# DRIVER_B.net
KiCad netlist of a schematic drawn in Altium Designer
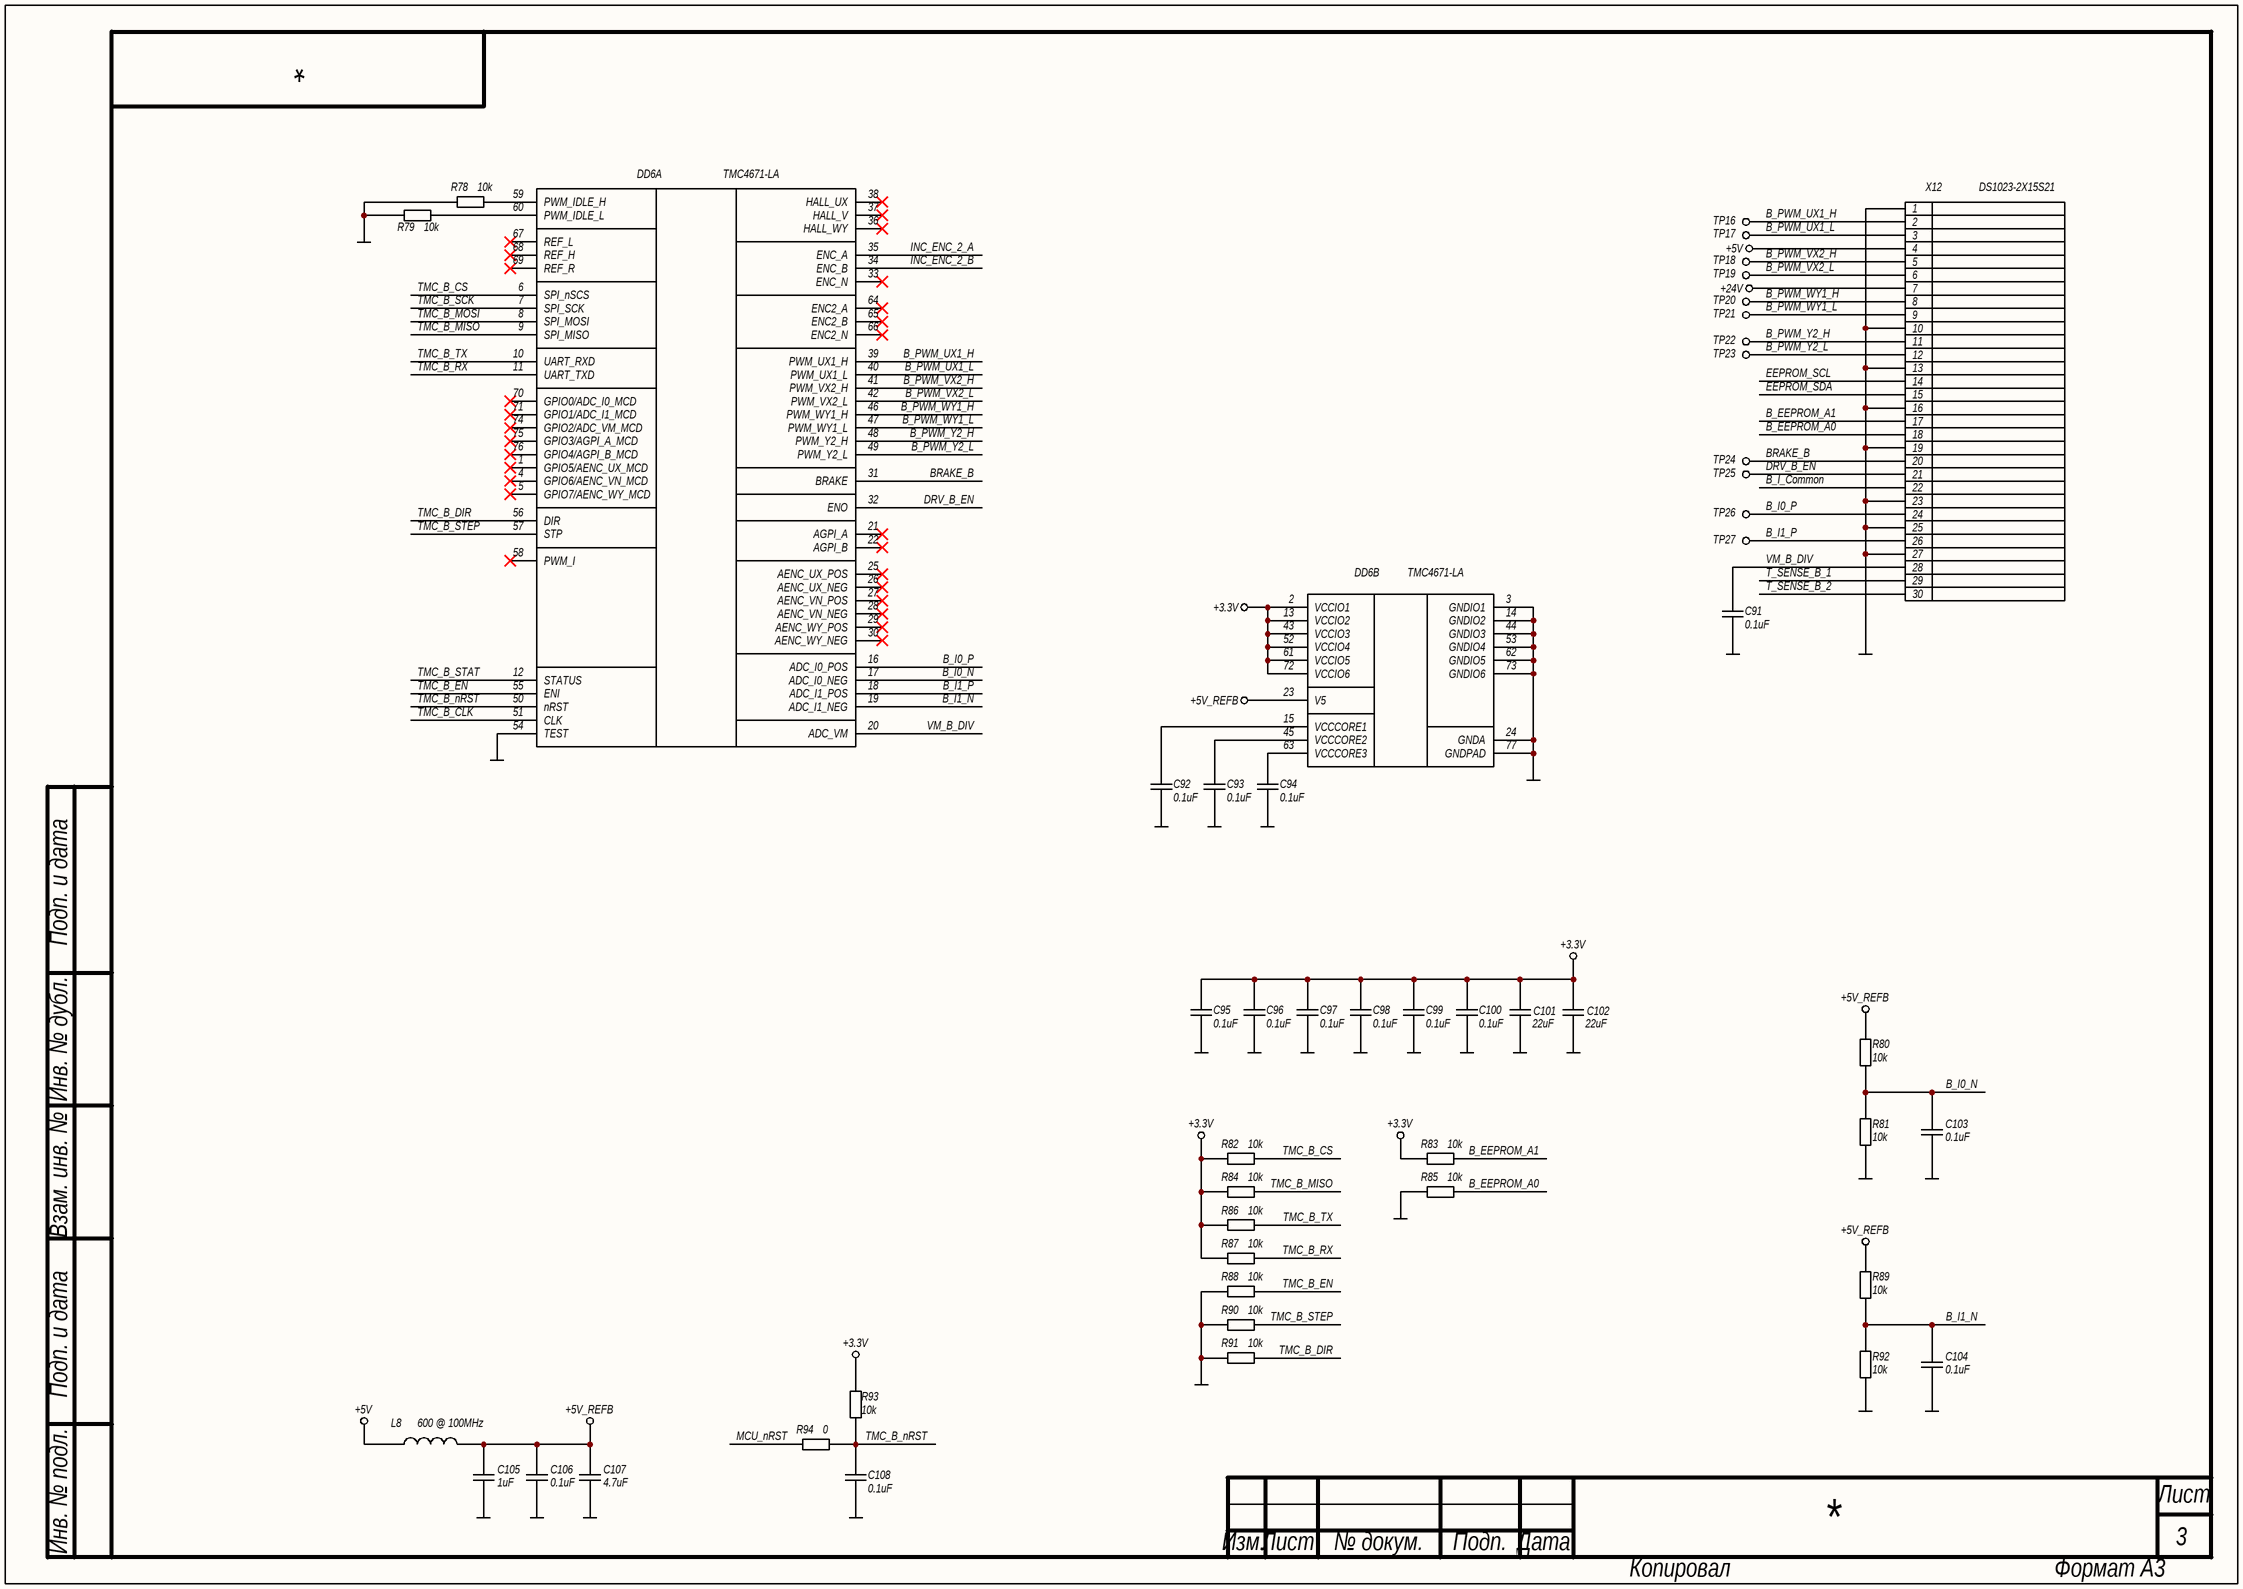
[diagram p0: DRIVER_B.SchDoc]

(export (version "E")
  (design (tool "Eeschema 10.0.6"))
  (components
    (comp (ref "C91")
      (value "0.1uF")
      (footprint "C0603N")
      (description "Конденсатор")
      (libsource (lib "Components Library") (part "CAP_FIXED"))
    )
    (comp (ref "C92")
      (value "0.1uF")
      (footprint "C0603N")
      (description "Конденсатор")
      (libsource (lib "Components Library") (part "CAP_FIXED"))
    )
    (comp (ref "C93")
      (value "0.1uF")
      (footprint "C0603N")
      (description "Конденсатор")
      (libsource (lib "Components Library") (part "CAP_FIXED"))
    )
    (comp (ref "C94")
      (value "0.1uF")
      (footprint "C0603N")
      (description "Конденсатор")
      (libsource (lib "Components Library") (part "CAP_FIXED"))
    )
    (comp (ref "C95")
      (value "0.1uF")
      (footprint "C0603N")
      (description "Конденсатор")
      (libsource (lib "Components Library") (part "CAP_FIXED"))
    )
    (comp (ref "C96")
      (value "0.1uF")
      (footprint "C0603N")
      (description "Конденсатор")
      (libsource (lib "Components Library") (part "CAP_FIXED"))
    )
    (comp (ref "C97")
      (value "0.1uF")
      (footprint "C0603N")
      (description "Конденсатор")
      (libsource (lib "Components Library") (part "CAP_FIXED"))
    )
    (comp (ref "C98")
      (value "0.1uF")
      (footprint "C0603N")
      (description "Конденсатор")
      (libsource (lib "Components Library") (part "CAP_FIXED"))
    )
    (comp (ref "C99")
      (value "0.1uF")
      (footprint "C0603N")
      (description "Конденсатор")
      (libsource (lib "Components Library") (part "CAP_FIXED"))
    )
    (comp (ref "C100")
      (value "0.1uF")
      (footprint "C0603N")
      (description "Конденсатор")
      (libsource (lib "Components Library") (part "CAP_FIXED"))
    )
    (comp (ref "C101")
      (value "22uF")
      (footprint "C0805N")
      (description "Конденсатор")
      (libsource (lib "Components Library") (part "CAP_FIXED"))
    )
    (comp (ref "C102")
      (value "22uF")
      (footprint "C0805N")
      (description "Конденсатор")
      (libsource (lib "Components Library") (part "CAP_FIXED"))
    )
    (comp (ref "C103")
      (value "0.1uF")
      (footprint "C0603N")
      (description "Конденсатор")
      (libsource (lib "Components Library") (part "CAP_FIXED"))
    )
    (comp (ref "C104")
      (value "0.1uF")
      (footprint "C0603N")
      (description "Конденсатор")
      (libsource (lib "Components Library") (part "CAP_FIXED"))
    )
    (comp (ref "C105")
      (value "1uF")
      (footprint "C0603N")
      (description "Конденсатор")
      (libsource (lib "Components Library") (part "CAP_FIXED"))
    )
    (comp (ref "C106")
      (value "0.1uF")
      (footprint "C0603N")
      (description "Конденсатор")
      (libsource (lib "Components Library") (part "CAP_FIXED"))
    )
    (comp (ref "C107")
      (value "4.7uF")
      (footprint "C0603N")
      (description "Конденсатор")
      (libsource (lib "Components Library") (part "CAP_FIXED"))
    )
    (comp (ref "C108")
      (value "0.1uF")
      (footprint "C0603N")
      (description "Конденсатор")
      (libsource (lib "Components Library") (part "CAP_FIXED"))
    )
    (comp (ref "DD6")
      (value "TMC4671-LA")
      (footprint "QFN76-EP")
      (description "Микросхема драйвер двигателя")
      (libsource (lib "Components Library") (part "TMC4671-LA"))
    )
    (comp (ref "L8")
      (value "600 @ 100MHz")
      (footprint "FB0603N")
      (description "Фильтр ЭМП индуктивный")
      (libsource (lib "Components Library") (part "IND_FILTER"))
    )
    (comp (ref "R78")
      (value "10k")
      (footprint "R0603N")
      (description "Резистор")
      (libsource (lib "Components Library") (part "RES_FIXED"))
    )
    (comp (ref "R79")
      (value "10k")
      (footprint "R0603N")
      (description "Резистор")
      (libsource (lib "Components Library") (part "RES_FIXED"))
    )
    (comp (ref "R80")
      (value "10k")
      (footprint "R0603N")
      (description "Резистор")
      (libsource (lib "") (part "RES_FIXED_1"))
    )
    (comp (ref "R81")
      (value "10k")
      (footprint "R0603N")
      (description "Резистор")
      (libsource (lib "") (part "RES_FIXED_1"))
    )
    (comp (ref "R82")
      (value "10k")
      (footprint "R0603N")
      (description "Резистор")
      (libsource (lib "Components Library") (part "RES_FIXED"))
    )
    (comp (ref "R83")
      (value "10k")
      (footprint "R0603N")
      (description "Резистор")
      (libsource (lib "Components Library") (part "RES_FIXED"))
    )
    (comp (ref "R84")
      (value "10k")
      (footprint "R0603N")
      (description "Резистор")
      (libsource (lib "Components Library") (part "RES_FIXED"))
    )
    (comp (ref "R85")
      (value "10k")
      (footprint "R0603N")
      (description "Резистор")
      (libsource (lib "Components Library") (part "RES_FIXED"))
    )
    (comp (ref "R86")
      (value "10k")
      (footprint "R0603N")
      (description "Резистор")
      (libsource (lib "Components Library") (part "RES_FIXED"))
    )
    (comp (ref "R87")
      (value "10k")
      (footprint "R0603N")
      (description "Резистор")
      (libsource (lib "Components Library") (part "RES_FIXED"))
    )
    (comp (ref "R88")
      (value "10k")
      (footprint "R0603N")
      (description "Резистор")
      (libsource (lib "Components Library") (part "RES_FIXED"))
    )
    (comp (ref "R89")
      (value "10k")
      (footprint "R0603N")
      (description "Резистор")
      (libsource (lib "") (part "RES_FIXED_1"))
    )
    (comp (ref "R90")
      (value "10k")
      (footprint "R0603N")
      (description "Резистор")
      (libsource (lib "Components Library") (part "RES_FIXED"))
    )
    (comp (ref "R91")
      (value "10k")
      (footprint "R0603N")
      (description "Резистор")
      (libsource (lib "Components Library") (part "RES_FIXED"))
    )
    (comp (ref "R92")
      (value "10k")
      (footprint "R0603N")
      (description "Резистор")
      (libsource (lib "") (part "RES_FIXED_1"))
    )
    (comp (ref "R93")
      (value "10k")
      (footprint "R0603N")
      (description "Резистор")
      (libsource (lib "") (part "RES_FIXED_1"))
    )
    (comp (ref "R94")
      (value "0")
      (footprint "R0603N")
      (description "Резистор")
      (libsource (lib "Components Library") (part "RES_FIXED"))
    )
    (comp (ref "TP16")
      (value "TEST_POINT")
      (footprint "TP_RPAD_0.8MM")
      (description "Контрольная точка")
      (libsource (lib "Components Library") (part "TEST_POINT"))
    )
    (comp (ref "TP17")
      (value "TEST_POINT")
      (footprint "TP_RPAD_0.8MM")
      (description "Контрольная точка")
      (libsource (lib "Components Library") (part "TEST_POINT"))
    )
    (comp (ref "TP18")
      (value "TEST_POINT")
      (footprint "TP_RPAD_0.8MM")
      (description "Контрольная точка")
      (libsource (lib "Components Library") (part "TEST_POINT"))
    )
    (comp (ref "TP19")
      (value "TEST_POINT")
      (footprint "TP_RPAD_0.8MM")
      (description "Контрольная точка")
      (libsource (lib "Components Library") (part "TEST_POINT"))
    )
    (comp (ref "TP20")
      (value "TEST_POINT")
      (footprint "TP_RPAD_0.8MM")
      (description "Контрольная точка")
      (libsource (lib "Components Library") (part "TEST_POINT"))
    )
    (comp (ref "TP21")
      (value "TEST_POINT")
      (footprint "TP_RPAD_0.8MM")
      (description "Контрольная точка")
      (libsource (lib "Components Library") (part "TEST_POINT"))
    )
    (comp (ref "TP22")
      (value "TEST_POINT")
      (footprint "TP_RPAD_0.8MM")
      (description "Контрольная точка")
      (libsource (lib "Components Library") (part "TEST_POINT"))
    )
    (comp (ref "TP23")
      (value "TEST_POINT")
      (footprint "TP_RPAD_0.8MM")
      (description "Контрольная точка")
      (libsource (lib "Components Library") (part "TEST_POINT"))
    )
    (comp (ref "TP24")
      (value "TEST_POINT")
      (footprint "TP_RPAD_0.8MM")
      (description "Контрольная точка")
      (libsource (lib "Components Library") (part "TEST_POINT"))
    )
    (comp (ref "TP25")
      (value "TEST_POINT")
      (footprint "TP_RPAD_0.8MM")
      (description "Контрольная точка")
      (libsource (lib "Components Library") (part "TEST_POINT"))
    )
    (comp (ref "TP26")
      (value "TEST_POINT")
      (footprint "TP_RPAD_0.8MM")
      (description "Контрольная точка")
      (libsource (lib "Components Library") (part "TEST_POINT"))
    )
    (comp (ref "TP27")
      (value "TEST_POINT")
      (footprint "TP_RPAD_0.8MM")
      (description "Контрольная точка")
      (libsource (lib "Components Library") (part "TEST_POINT"))
    )
    (comp (ref "X12")
      (value "DS1023-2X15S21")
      (footprint "2.54_2X15_SOCKET_HEADER")
      (description "Разъем, 30 контактов")
      (libsource (lib "Components Library") (part "Connector 30"))
    )
  )
  (nets
    (net (code "1") (name "+3.3V") (class "Default")
      (node (ref "C100") (pin "2") (pinfunction "2_2") (pintype "passive"))
      (node (ref "C101") (pin "2") (pinfunction "2_2") (pintype "passive"))
      (node (ref "C102") (pin "2") (pinfunction "2_2") (pintype "passive"))
      (node (ref "C95") (pin "2") (pinfunction "2_2") (pintype "passive"))
      (node (ref "C96") (pin "2") (pinfunction "2_2") (pintype "passive"))
      (node (ref "C97") (pin "2") (pinfunction "2_2") (pintype "passive"))
      (node (ref "C98") (pin "2") (pinfunction "2_2") (pintype "passive"))
      (node (ref "C99") (pin "2") (pinfunction "2_2") (pintype "passive"))
      (node (ref "DD6") (pin "13") (pinfunction "VCCIO2_13") (pintype "power_in"))
      (node (ref "DD6") (pin "2") (pinfunction "VCCIO1_2") (pintype "power_in"))
      (node (ref "DD6") (pin "43") (pinfunction "VCCIO3_43") (pintype "power_in"))
      (node (ref "DD6") (pin "52") (pinfunction "VCCIO4_52") (pintype "power_in"))
      (node (ref "DD6") (pin "61") (pinfunction "VCCIO5_61") (pintype "power_in"))
      (node (ref "DD6") (pin "72") (pinfunction "VCCIO6_72") (pintype "power_in"))
      (node (ref "R82") (pin "2") (pinfunction "2_2") (pintype "passive"))
      (node (ref "R83") (pin "2") (pinfunction "2_2") (pintype "passive"))
      (node (ref "R84") (pin "2") (pinfunction "2_2") (pintype "passive"))
      (node (ref "R86") (pin "2") (pinfunction "2_2") (pintype "passive"))
      (node (ref "R87") (pin "2") (pinfunction "2_2") (pintype "passive"))
      (node (ref "R93") (pin "2") (pinfunction "2_2") (pintype "passive"))
    )
    (net (code "2") (name "+5V") (class "Default")
      (node (ref "L8") (pin "1") (pinfunction "1_1") (pintype "passive"))
      (node (ref "X12") (pin "4") (pinfunction "4_4") (pintype "power_in"))
    )
    (net (code "3") (name "+5V_REFB") (class "Default")
      (node (ref "C105") (pin "2") (pinfunction "2_2") (pintype "passive"))
      (node (ref "C106") (pin "2") (pinfunction "2_2") (pintype "passive"))
      (node (ref "C107") (pin "2") (pinfunction "2_2") (pintype "passive"))
      (node (ref "DD6") (pin "23") (pinfunction "V5_23") (pintype "power_in"))
      (node (ref "L8") (pin "2") (pinfunction "2_2") (pintype "passive"))
      (node (ref "R80") (pin "2") (pinfunction "2_2") (pintype "passive"))
      (node (ref "R89") (pin "2") (pinfunction "2_2") (pintype "passive"))
    )
    (net (code "4") (name "+24V") (class "Default")
      (node (ref "X12") (pin "7") (pinfunction "7_7") (pintype "power_in"))
    )
    (net (code "5") (name "/BRAKE_B") (class "Default")
      (node (ref "DD6") (pin "31") (pinfunction "BRAKE_31") (pintype "power_in"))
      (node (ref "TP24") (pin "1") (pinfunction "1_1") (pintype "passive"))
      (node (ref "X12") (pin "20") (pinfunction "20_20") (pintype "power_in"))
    )
    (net (code "6") (name "/B_EEPROM_A0") (class "Default")
      (node (ref "R85") (pin "1") (pinfunction "1_1") (pintype "passive"))
      (node (ref "X12") (pin "18") (pinfunction "18_18") (pintype "power_in"))
    )
    (net (code "7") (name "/B_EEPROM_A1") (class "Default")
      (node (ref "R83") (pin "1") (pinfunction "1_1") (pintype "passive"))
      (node (ref "X12") (pin "17") (pinfunction "17_17") (pintype "power_in"))
    )
    (net (code "8") (name "/B_I0_N") (class "Default")
      (node (ref "C103") (pin "2") (pinfunction "2_2") (pintype "passive"))
      (node (ref "DD6") (pin "17") (pinfunction "ADC_I0_NEG_17") (pintype "power_in"))
      (node (ref "R80") (pin "1") (pinfunction "1_1") (pintype "passive"))
      (node (ref "R81") (pin "2") (pinfunction "2_2") (pintype "passive"))
    )
    (net (code "9") (name "/B_I0_P") (class "Default")
      (node (ref "DD6") (pin "16") (pinfunction "ADC_I0_POS_16") (pintype "power_in"))
      (node (ref "TP26") (pin "1") (pinfunction "1_1") (pintype "passive"))
      (node (ref "X12") (pin "24") (pinfunction "24_24") (pintype "power_in"))
    )
    (net (code "10") (name "/B_I1_N") (class "Default")
      (node (ref "C104") (pin "2") (pinfunction "2_2") (pintype "passive"))
      (node (ref "DD6") (pin "19") (pinfunction "ADC_I1_NEG_19") (pintype "power_in"))
      (node (ref "R89") (pin "1") (pinfunction "1_1") (pintype "passive"))
      (node (ref "R92") (pin "2") (pinfunction "2_2") (pintype "passive"))
    )
    (net (code "11") (name "/B_I1_P") (class "Default")
      (node (ref "DD6") (pin "18") (pinfunction "ADC_I1_POS_18") (pintype "power_in"))
      (node (ref "TP27") (pin "1") (pinfunction "1_1") (pintype "passive"))
      (node (ref "X12") (pin "26") (pinfunction "26_26") (pintype "power_in"))
    )
    (net (code "12") (name "/B_I_Common") (class "Default")
      (node (ref "X12") (pin "22") (pinfunction "22_22") (pintype "power_in"))
    )
    (net (code "13") (name "/B_PWM_UX1_H") (class "Default")
      (node (ref "DD6") (pin "39") (pinfunction "PWM_UX1_H_39") (pintype "power_in"))
      (node (ref "TP16") (pin "1") (pinfunction "1_1") (pintype "passive"))
      (node (ref "X12") (pin "2") (pinfunction "2_2") (pintype "power_in"))
    )
    (net (code "14") (name "/B_PWM_UX1_L") (class "Default")
      (node (ref "DD6") (pin "40") (pinfunction "PWM_UX1_L_40") (pintype "power_in"))
      (node (ref "TP17") (pin "1") (pinfunction "1_1") (pintype "passive"))
      (node (ref "X12") (pin "3") (pinfunction "3_3") (pintype "power_in"))
    )
    (net (code "15") (name "/B_PWM_VX2_H") (class "Default")
      (node (ref "DD6") (pin "41") (pinfunction "PWM_VX2_H_41") (pintype "power_in"))
      (node (ref "TP18") (pin "1") (pinfunction "1_1") (pintype "passive"))
      (node (ref "X12") (pin "5") (pinfunction "5_5") (pintype "power_in"))
    )
    (net (code "16") (name "/B_PWM_VX2_L") (class "Default")
      (node (ref "DD6") (pin "42") (pinfunction "PWM_VX2_L_42") (pintype "power_in"))
      (node (ref "TP19") (pin "1") (pinfunction "1_1") (pintype "passive"))
      (node (ref "X12") (pin "6") (pinfunction "6_6") (pintype "power_in"))
    )
    (net (code "17") (name "/B_PWM_WY1_H") (class "Default")
      (node (ref "DD6") (pin "46") (pinfunction "PWM_WY1_H_46") (pintype "power_in"))
      (node (ref "TP20") (pin "1") (pinfunction "1_1") (pintype "passive"))
      (node (ref "X12") (pin "8") (pinfunction "8_8") (pintype "power_in"))
    )
    (net (code "18") (name "/B_PWM_WY1_L") (class "Default")
      (node (ref "DD6") (pin "47") (pinfunction "PWM_WY1_L_47") (pintype "power_in"))
      (node (ref "TP21") (pin "1") (pinfunction "1_1") (pintype "passive"))
      (node (ref "X12") (pin "9") (pinfunction "9_9") (pintype "power_in"))
    )
    (net (code "19") (name "/B_PWM_Y2_H") (class "Default")
      (node (ref "DD6") (pin "48") (pinfunction "PWM_Y2_H_48") (pintype "power_in"))
      (node (ref "TP22") (pin "1") (pinfunction "1_1") (pintype "passive"))
      (node (ref "X12") (pin "11") (pinfunction "11_11") (pintype "power_in"))
    )
    (net (code "20") (name "/B_PWM_Y2_L") (class "Default")
      (node (ref "DD6") (pin "49") (pinfunction "PWM_Y2_L_49") (pintype "power_in"))
      (node (ref "TP23") (pin "1") (pinfunction "1_1") (pintype "passive"))
      (node (ref "X12") (pin "12") (pinfunction "12_12") (pintype "power_in"))
    )
    (net (code "21") (name "/DRV_B_EN") (class "Default")
      (node (ref "DD6") (pin "32") (pinfunction "ENO_32") (pintype "power_in"))
      (node (ref "TP25") (pin "1") (pinfunction "1_1") (pintype "passive"))
      (node (ref "X12") (pin "21") (pinfunction "21_21") (pintype "power_in"))
    )
    (net (code "22") (name "/EEPROM_SCL") (class "Default")
      (node (ref "X12") (pin "14") (pinfunction "14_14") (pintype "power_in"))
    )
    (net (code "23") (name "/EEPROM_SDA") (class "Default")
      (node (ref "X12") (pin "15") (pinfunction "15_15") (pintype "power_in"))
    )
    (net (code "24") (name "/INC_ENC_2_A") (class "Default")
      (node (ref "DD6") (pin "35") (pinfunction "ENC_A_35") (pintype "power_in"))
    )
    (net (code "25") (name "/INC_ENC_2_B") (class "Default")
      (node (ref "DD6") (pin "34") (pinfunction "ENC_B_34") (pintype "power_in"))
    )
    (net (code "26") (name "/MCU_nRST") (class "Default")
      (node (ref "R94") (pin "2") (pinfunction "2_2") (pintype "passive"))
    )
    (net (code "27") (name "/TMC_B_CLK") (class "Default")
      (node (ref "DD6") (pin "51") (pinfunction "CLK_51") (pintype "power_in"))
    )
    (net (code "28") (name "/TMC_B_CS") (class "Default")
      (node (ref "DD6") (pin "6") (pinfunction "SPI_nSCS_6") (pintype "power_in"))
      (node (ref "R82") (pin "1") (pinfunction "1_1") (pintype "passive"))
    )
    (net (code "29") (name "/TMC_B_DIR") (class "Default")
      (node (ref "DD6") (pin "56") (pinfunction "DIR_56") (pintype "power_in"))
      (node (ref "R91") (pin "1") (pinfunction "1_1") (pintype "passive"))
    )
    (net (code "30") (name "/TMC_B_EN") (class "Default")
      (node (ref "DD6") (pin "55") (pinfunction "ENI_55") (pintype "power_in"))
      (node (ref "R88") (pin "1") (pinfunction "1_1") (pintype "passive"))
    )
    (net (code "31") (name "/TMC_B_MISO") (class "Default")
      (node (ref "DD6") (pin "9") (pinfunction "SPI_MISO_9") (pintype "power_in"))
      (node (ref "R84") (pin "1") (pinfunction "1_1") (pintype "passive"))
    )
    (net (code "32") (name "/TMC_B_MOSI") (class "Default")
      (node (ref "DD6") (pin "8") (pinfunction "SPI_MOSI_8") (pintype "power_in"))
    )
    (net (code "33") (name "/TMC_B_RX") (class "Default")
      (node (ref "DD6") (pin "11") (pinfunction "UART_TXD_11") (pintype "power_in"))
      (node (ref "R87") (pin "1") (pinfunction "1_1") (pintype "passive"))
    )
    (net (code "34") (name "/TMC_B_SCK") (class "Default")
      (node (ref "DD6") (pin "7") (pinfunction "SPI_SCK_7") (pintype "power_in"))
    )
    (net (code "35") (name "/TMC_B_STAT") (class "Default")
      (node (ref "DD6") (pin "12") (pinfunction "STATUS_12") (pintype "power_in"))
    )
    (net (code "36") (name "/TMC_B_STEP") (class "Default")
      (node (ref "DD6") (pin "57") (pinfunction "STP_57") (pintype "power_in"))
      (node (ref "R90") (pin "1") (pinfunction "1_1") (pintype "passive"))
    )
    (net (code "37") (name "/TMC_B_TX") (class "Default")
      (node (ref "DD6") (pin "10") (pinfunction "UART_RXD_10") (pintype "power_in"))
      (node (ref "R86") (pin "1") (pinfunction "1_1") (pintype "passive"))
    )
    (net (code "38") (name "/TMC_B_nRST") (class "Default")
      (node (ref "C108") (pin "2") (pinfunction "2_2") (pintype "passive"))
      (node (ref "DD6") (pin "50") (pinfunction "nRST_50") (pintype "power_in"))
      (node (ref "R93") (pin "1") (pinfunction "1_1") (pintype "passive"))
      (node (ref "R94") (pin "1") (pinfunction "1_1") (pintype "passive"))
    )
    (net (code "39") (name "/T_SENSE_B_1") (class "Default")
      (node (ref "X12") (pin "29") (pinfunction "29_29") (pintype "power_in"))
    )
    (net (code "40") (name "/T_SENSE_B_2") (class "Default")
      (node (ref "X12") (pin "30") (pinfunction "30_30") (pintype "power_in"))
    )
    (net (code "41") (name "/VM_B_DIV") (class "Default")
      (node (ref "C91") (pin "2") (pinfunction "2_2") (pintype "passive"))
      (node (ref "DD6") (pin "20") (pinfunction "ADC_VM_20") (pintype "power_in"))
      (node (ref "X12") (pin "28") (pinfunction "28_28") (pintype "power_in"))
    )
    (net (code "42") (name "GND") (class "Default")
      (node (ref "C100") (pin "1") (pinfunction "1_1") (pintype "passive"))
      (node (ref "C101") (pin "1") (pinfunction "1_1") (pintype "passive"))
      (node (ref "C102") (pin "1") (pinfunction "1_1") (pintype "passive"))
      (node (ref "C103") (pin "1") (pinfunction "1_1") (pintype "passive"))
      (node (ref "C104") (pin "1") (pinfunction "1_1") (pintype "passive"))
      (node (ref "C105") (pin "1") (pinfunction "1_1") (pintype "passive"))
      (node (ref "C106") (pin "1") (pinfunction "1_1") (pintype "passive"))
      (node (ref "C107") (pin "1") (pinfunction "1_1") (pintype "passive"))
      (node (ref "C108") (pin "1") (pinfunction "1_1") (pintype "passive"))
      (node (ref "C91") (pin "1") (pinfunction "1_1") (pintype "passive"))
      (node (ref "C92") (pin "1") (pinfunction "1_1") (pintype "passive"))
      (node (ref "C93") (pin "1") (pinfunction "1_1") (pintype "passive"))
      (node (ref "C94") (pin "1") (pinfunction "1_1") (pintype "passive"))
      (node (ref "C95") (pin "1") (pinfunction "1_1") (pintype "passive"))
      (node (ref "C96") (pin "1") (pinfunction "1_1") (pintype "passive"))
      (node (ref "C97") (pin "1") (pinfunction "1_1") (pintype "passive"))
      (node (ref "C98") (pin "1") (pinfunction "1_1") (pintype "passive"))
      (node (ref "C99") (pin "1") (pinfunction "1_1") (pintype "passive"))
      (node (ref "DD6") (pin "14") (pinfunction "GNDIO2_14") (pintype "power_in"))
      (node (ref "DD6") (pin "24") (pinfunction "GNDA_24") (pintype "power_in"))
      (node (ref "DD6") (pin "3") (pinfunction "GNDIO1_3") (pintype "power_in"))
      (node (ref "DD6") (pin "44") (pinfunction "GNDIO3_44") (pintype "power_in"))
      (node (ref "DD6") (pin "53") (pinfunction "GNDIO4_53") (pintype "power_in"))
      (node (ref "DD6") (pin "54") (pinfunction "TEST_54") (pintype "power_in"))
      (node (ref "DD6") (pin "62") (pinfunction "GNDIO5_62") (pintype "power_in"))
      (node (ref "DD6") (pin "73") (pinfunction "GNDIO6_73") (pintype "power_in"))
      (node (ref "DD6") (pin "77") (pinfunction "GNDPAD_77") (pintype "power_in"))
      (node (ref "R78") (pin "2") (pinfunction "2_2") (pintype "passive"))
      (node (ref "R79") (pin "2") (pinfunction "2_2") (pintype "passive"))
      (node (ref "R81") (pin "1") (pinfunction "1_1") (pintype "passive"))
      (node (ref "R85") (pin "2") (pinfunction "2_2") (pintype "passive"))
      (node (ref "R88") (pin "2") (pinfunction "2_2") (pintype "passive"))
      (node (ref "R90") (pin "2") (pinfunction "2_2") (pintype "passive"))
      (node (ref "R91") (pin "2") (pinfunction "2_2") (pintype "passive"))
      (node (ref "R92") (pin "1") (pinfunction "1_1") (pintype "passive"))
      (node (ref "X12") (pin "1") (pinfunction "1_1") (pintype "power_in"))
      (node (ref "X12") (pin "10") (pinfunction "10_10") (pintype "power_in"))
      (node (ref "X12") (pin "13") (pinfunction "13_13") (pintype "power_in"))
      (node (ref "X12") (pin "16") (pinfunction "16_16") (pintype "power_in"))
      (node (ref "X12") (pin "19") (pinfunction "19_19") (pintype "power_in"))
      (node (ref "X12") (pin "23") (pinfunction "23_23") (pintype "power_in"))
      (node (ref "X12") (pin "25") (pinfunction "25_25") (pintype "power_in"))
      (node (ref "X12") (pin "27") (pinfunction "27_27") (pintype "power_in"))
    )
    (net (code "43") (name "Net-(DD6A-PWM_IDLE_H)") (class "Default")
      (node (ref "DD6") (pin "59") (pinfunction "PWM_IDLE_H_59") (pintype "power_in"))
      (node (ref "R78") (pin "1") (pinfunction "1_1") (pintype "passive"))
    )
    (net (code "44") (name "Net-(DD6A-PWM_IDLE_L)") (class "Default")
      (node (ref "DD6") (pin "60") (pinfunction "PWM_IDLE_L_60") (pintype "power_in"))
      (node (ref "R79") (pin "1") (pinfunction "1_1") (pintype "passive"))
    )
    (net (code "45") (name "Net-(DD6B-VCCCORE1)") (class "Default")
      (node (ref "C92") (pin "2") (pinfunction "2_2") (pintype "passive"))
      (node (ref "DD6") (pin "15") (pinfunction "VCCCORE1_15") (pintype "power_in"))
    )
    (net (code "46") (name "Net-(DD6B-VCCCORE2)") (class "Default")
      (node (ref "C93") (pin "2") (pinfunction "2_2") (pintype "passive"))
      (node (ref "DD6") (pin "45") (pinfunction "VCCCORE2_45") (pintype "power_in"))
    )
    (net (code "47") (name "Net-(DD6B-VCCCORE3)") (class "Default")
      (node (ref "C94") (pin "2") (pinfunction "2_2") (pintype "passive"))
      (node (ref "DD6") (pin "63") (pinfunction "VCCCORE3_63") (pintype "power_in"))
    )
    (net (code "48") (name "unconnected-(DD6A-AENC_UX_NEG-Pad26)") (class "Default")
      (node (ref "DD6") (pin "26") (pinfunction "AENC_UX_NEG_26") (pintype "power_in+no_connect"))
    )
    (net (code "49") (name "unconnected-(DD6A-AENC_UX_POS-Pad25)") (class "Default")
      (node (ref "DD6") (pin "25") (pinfunction "AENC_UX_POS_25") (pintype "power_in+no_connect"))
    )
    (net (code "50") (name "unconnected-(DD6A-AENC_VN_NEG-Pad28)") (class "Default")
      (node (ref "DD6") (pin "28") (pinfunction "AENC_VN_NEG_28") (pintype "power_in+no_connect"))
    )
    (net (code "51") (name "unconnected-(DD6A-AENC_VN_POS-Pad27)") (class "Default")
      (node (ref "DD6") (pin "27") (pinfunction "AENC_VN_POS_27") (pintype "power_in+no_connect"))
    )
    (net (code "52") (name "unconnected-(DD6A-AENC_WY_NEG-Pad30)") (class "Default")
      (node (ref "DD6") (pin "30") (pinfunction "AENC_WY_NEG_30") (pintype "power_in+no_connect"))
    )
    (net (code "53") (name "unconnected-(DD6A-AENC_WY_POS-Pad29)") (class "Default")
      (node (ref "DD6") (pin "29") (pinfunction "AENC_WY_POS_29") (pintype "power_in+no_connect"))
    )
    (net (code "54") (name "unconnected-(DD6A-AGPI_A-Pad21)") (class "Default")
      (node (ref "DD6") (pin "21") (pinfunction "AGPI_A_21") (pintype "power_in+no_connect"))
    )
    (net (code "55") (name "unconnected-(DD6A-AGPI_B-Pad22)") (class "Default")
      (node (ref "DD6") (pin "22") (pinfunction "AGPI_B_22") (pintype "power_in+no_connect"))
    )
    (net (code "56") (name "unconnected-(DD6A-ENC2_A-Pad64)") (class "Default")
      (node (ref "DD6") (pin "64") (pinfunction "ENC2_A_64") (pintype "power_in+no_connect"))
    )
    (net (code "57") (name "unconnected-(DD6A-ENC2_B-Pad65)") (class "Default")
      (node (ref "DD6") (pin "65") (pinfunction "ENC2_B_65") (pintype "power_in+no_connect"))
    )
    (net (code "58") (name "unconnected-(DD6A-ENC2_N-Pad66)") (class "Default")
      (node (ref "DD6") (pin "66") (pinfunction "ENC2_N_66") (pintype "power_in+no_connect"))
    )
    (net (code "59") (name "unconnected-(DD6A-ENC_N-Pad33)") (class "Default")
      (node (ref "DD6") (pin "33") (pinfunction "ENC_N_33") (pintype "power_in+no_connect"))
    )
    (net (code "60") (name "unconnected-(DD6A-GPIO0{slash}ADC_I0_MCD-Pad70)") (class "Default")
      (node (ref "DD6") (pin "70") (pinfunction "GPIO0/ADC_I0_MCD_70") (pintype "power_in+no_connect"))
    )
    (net (code "61") (name "unconnected-(DD6A-GPIO1{slash}ADC_I1_MCD-Pad71)") (class "Default")
      (node (ref "DD6") (pin "71") (pinfunction "GPIO1/ADC_I1_MCD_71") (pintype "power_in+no_connect"))
    )
    (net (code "62") (name "unconnected-(DD6A-GPIO2{slash}ADC_VM_MCD-Pad74)") (class "Default")
      (node (ref "DD6") (pin "74") (pinfunction "GPIO2/ADC_VM_MCD_74") (pintype "power_in+no_connect"))
    )
    (net (code "63") (name "unconnected-(DD6A-GPIO3{slash}AGPI_A_MCD-Pad75)") (class "Default")
      (node (ref "DD6") (pin "75") (pinfunction "GPIO3/AGPI_A_MCD_75") (pintype "power_in+no_connect"))
    )
    (net (code "64") (name "unconnected-(DD6A-GPIO4{slash}AGPI_B_MCD-Pad76)") (class "Default")
      (node (ref "DD6") (pin "76") (pinfunction "GPIO4/AGPI_B_MCD_76") (pintype "power_in+no_connect"))
    )
    (net (code "65") (name "unconnected-(DD6A-GPIO5{slash}AENC_UX_MCD-Pad1)") (class "Default")
      (node (ref "DD6") (pin "1") (pinfunction "GPIO5/AENC_UX_MCD_1") (pintype "power_in+no_connect"))
    )
    (net (code "66") (name "unconnected-(DD6A-GPIO6{slash}AENC_VN_MCD-Pad4)") (class "Default")
      (node (ref "DD6") (pin "4") (pinfunction "GPIO6/AENC_VN_MCD_4") (pintype "power_in+no_connect"))
    )
    (net (code "67") (name "unconnected-(DD6A-GPIO7{slash}AENC_WY_MCD-Pad5)") (class "Default")
      (node (ref "DD6") (pin "5") (pinfunction "GPIO7/AENC_WY_MCD_5") (pintype "power_in+no_connect"))
    )
    (net (code "68") (name "unconnected-(DD6A-HALL_UX-Pad38)") (class "Default")
      (node (ref "DD6") (pin "38") (pinfunction "HALL_UX_38") (pintype "power_in+no_connect"))
    )
    (net (code "69") (name "unconnected-(DD6A-HALL_V-Pad37)") (class "Default")
      (node (ref "DD6") (pin "37") (pinfunction "HALL_V_37") (pintype "power_in+no_connect"))
    )
    (net (code "70") (name "unconnected-(DD6A-HALL_WY-Pad36)") (class "Default")
      (node (ref "DD6") (pin "36") (pinfunction "HALL_WY_36") (pintype "power_in+no_connect"))
    )
    (net (code "71") (name "unconnected-(DD6A-PWM_I-Pad58)") (class "Default")
      (node (ref "DD6") (pin "58") (pinfunction "PWM_I_58") (pintype "power_in+no_connect"))
    )
    (net (code "72") (name "unconnected-(DD6A-REF_H-Pad68)") (class "Default")
      (node (ref "DD6") (pin "68") (pinfunction "REF_H_68") (pintype "power_in+no_connect"))
    )
    (net (code "73") (name "unconnected-(DD6A-REF_L-Pad67)") (class "Default")
      (node (ref "DD6") (pin "67") (pinfunction "REF_L_67") (pintype "power_in+no_connect"))
    )
    (net (code "74") (name "unconnected-(DD6A-REF_R-Pad69)") (class "Default")
      (node (ref "DD6") (pin "69") (pinfunction "REF_R_69") (pintype "power_in+no_connect"))
    )
  )
)
